# 4_cyber60-mx_periferals.net
KiCad netlist of a schematic drawn in Altium Designer
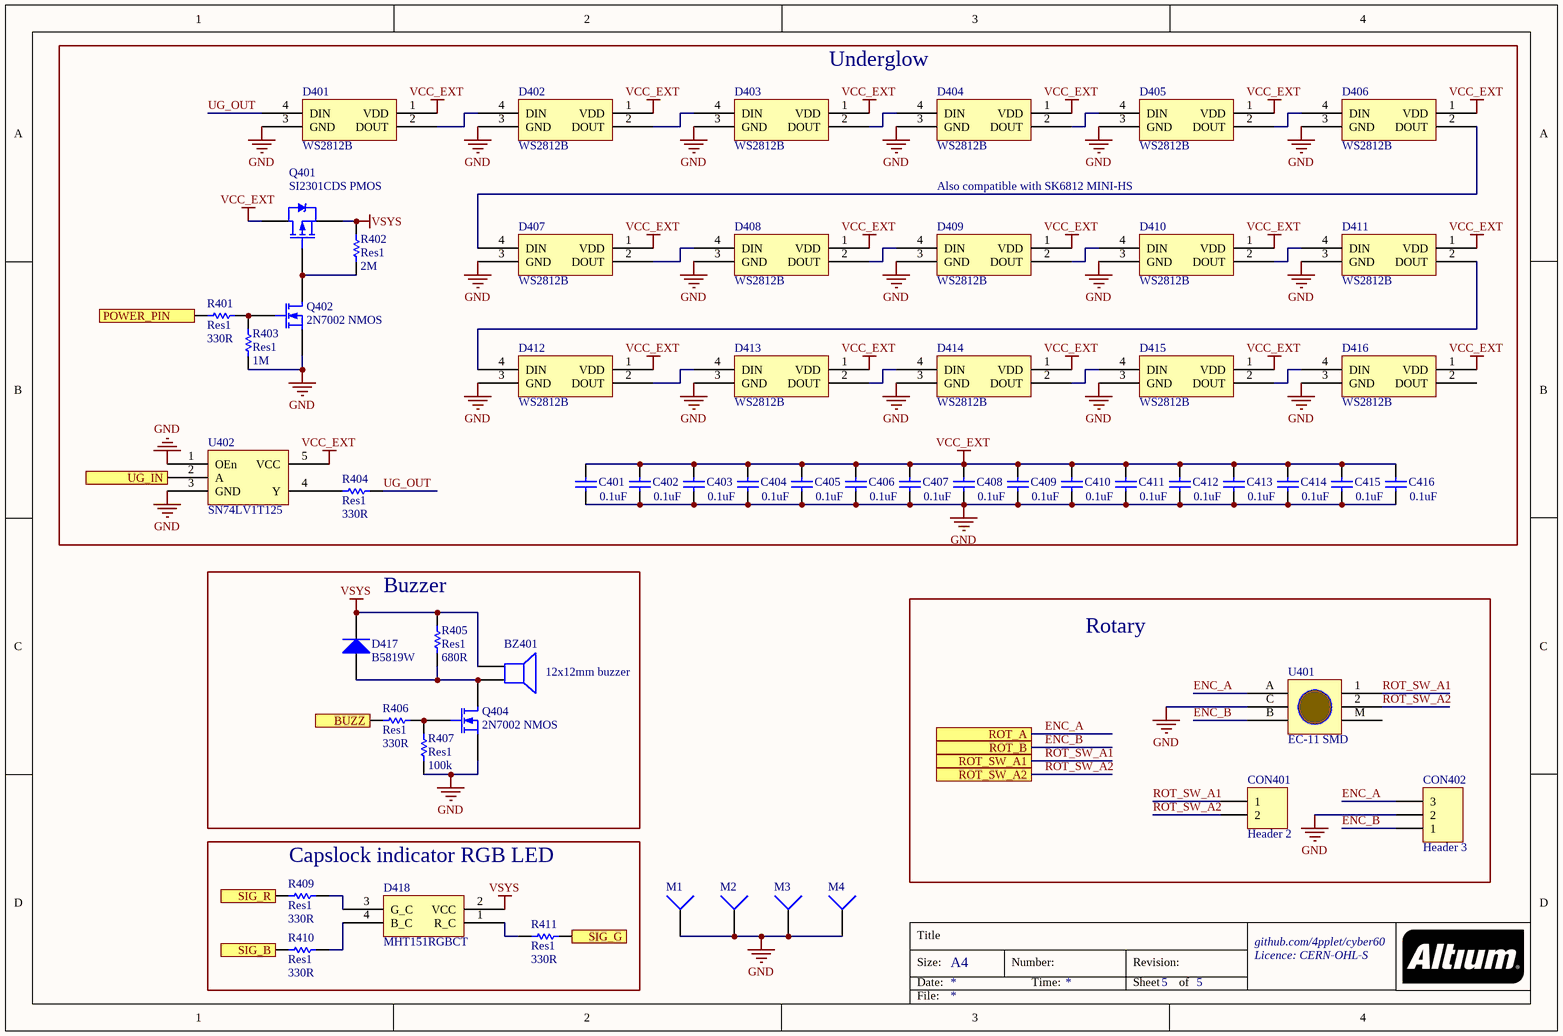
[diagram p0: 4_cyber60-mx_periferals.SchDoc]

(export (version "E")
  (design (tool "Eeschema 10.0.6"))
  (components
    (comp (ref "BZ401")
      (value "12x12mm buzzer")
      (footprint "buzzer 12x12")
      (description "Loudspeaker")
      (fields (field (name "LCSC PART #") "C409829") (field (name "MRF.PART") "YS-SBZ1230"))
      (libsource (lib "Miscellaneous Devices") (part "Speaker"))
    )
    (comp (ref "C401")
      (value "0.1uF")
      (footprint "C0603[1608]")
      (description "Capacitor")
      (fields (field (name "MFG") "KEMET") (field (name "LCSC PART #") "C14663"))
      (libsource (lib "Miscellaneous Devices") (part "Cap"))
    )
    (comp (ref "C402")
      (value "0.1uF")
      (footprint "C0603[1608]")
      (description "Capacitor")
      (fields (field (name "MFG") "KEMET") (field (name "LCSC PART #") "C14663"))
      (libsource (lib "Miscellaneous Devices") (part "Cap"))
    )
    (comp (ref "C403")
      (value "0.1uF")
      (footprint "C0603[1608]")
      (description "Capacitor")
      (fields (field (name "MFG") "KEMET") (field (name "LCSC PART #") "C14663"))
      (libsource (lib "Miscellaneous Devices") (part "Cap"))
    )
    (comp (ref "C404")
      (value "0.1uF")
      (footprint "C0603[1608]")
      (description "Capacitor")
      (fields (field (name "MFG") "KEMET") (field (name "LCSC PART #") "C14663"))
      (libsource (lib "Miscellaneous Devices") (part "Cap"))
    )
    (comp (ref "C405")
      (value "0.1uF")
      (footprint "C0603[1608]")
      (description "Capacitor")
      (fields (field (name "MFG") "KEMET") (field (name "LCSC PART #") "C14663"))
      (libsource (lib "Miscellaneous Devices") (part "Cap"))
    )
    (comp (ref "C406")
      (value "0.1uF")
      (footprint "C0603[1608]")
      (description "Capacitor")
      (fields (field (name "MFG") "KEMET") (field (name "LCSC PART #") "C14663"))
      (libsource (lib "Miscellaneous Devices") (part "Cap"))
    )
    (comp (ref "C407")
      (value "0.1uF")
      (footprint "C0603[1608]")
      (description "Capacitor")
      (fields (field (name "MFG") "KEMET") (field (name "LCSC PART #") "C14663"))
      (libsource (lib "Miscellaneous Devices") (part "Cap"))
    )
    (comp (ref "C408")
      (value "0.1uF")
      (footprint "C0603[1608]")
      (description "Capacitor")
      (fields (field (name "MFG") "KEMET") (field (name "LCSC PART #") "C14663"))
      (libsource (lib "Miscellaneous Devices") (part "Cap"))
    )
    (comp (ref "C409")
      (value "0.1uF")
      (footprint "C0603[1608]")
      (description "Capacitor")
      (fields (field (name "MFG") "KEMET") (field (name "LCSC PART #") "C14663"))
      (libsource (lib "Miscellaneous Devices") (part "Cap"))
    )
    (comp (ref "C410")
      (value "0.1uF")
      (footprint "C0603[1608]")
      (description "Capacitor")
      (fields (field (name "MFG") "KEMET") (field (name "LCSC PART #") "C14663"))
      (libsource (lib "Miscellaneous Devices") (part "Cap"))
    )
    (comp (ref "C411")
      (value "0.1uF")
      (footprint "C0603[1608]")
      (description "Capacitor")
      (fields (field (name "MFG") "KEMET") (field (name "LCSC PART #") "C14663"))
      (libsource (lib "Miscellaneous Devices") (part "Cap"))
    )
    (comp (ref "C412")
      (value "0.1uF")
      (footprint "C0603[1608]")
      (description "Capacitor")
      (fields (field (name "MFG") "KEMET") (field (name "LCSC PART #") "C14663"))
      (libsource (lib "Miscellaneous Devices") (part "Cap"))
    )
    (comp (ref "C413")
      (value "0.1uF")
      (footprint "C0603[1608]")
      (description "Capacitor")
      (fields (field (name "MFG") "KEMET") (field (name "LCSC PART #") "C14663"))
      (libsource (lib "Miscellaneous Devices") (part "Cap"))
    )
    (comp (ref "C414")
      (value "0.1uF")
      (footprint "C0603[1608]")
      (description "Capacitor")
      (fields (field (name "MFG") "KEMET") (field (name "LCSC PART #") "C14663"))
      (libsource (lib "Miscellaneous Devices") (part "Cap"))
    )
    (comp (ref "C415")
      (value "0.1uF")
      (footprint "C0603[1608]")
      (description "Capacitor")
      (fields (field (name "MFG") "KEMET") (field (name "LCSC PART #") "C14663"))
      (libsource (lib "Miscellaneous Devices") (part "Cap"))
    )
    (comp (ref "C416")
      (value "0.1uF")
      (footprint "C0603[1608]")
      (description "Capacitor")
      (fields (field (name "MFG") "KEMET") (field (name "LCSC PART #") "C14663"))
      (libsource (lib "Miscellaneous Devices") (part "Cap"))
    )
    (comp (ref "CON401")
      (value "Header 2")
      (footprint "HDR1X2")
      (description "Header, 2-Pin")
      (libsource (lib "Miscellaneous Connectors") (part "Header 2"))
    )
    (comp (ref "CON402")
      (value "Header 3")
      (footprint "HDR1X3")
      (description "Header, 3-Pin")
      (libsource (lib "Miscellaneous Connectors") (part "Header 3"))
    )
    (comp (ref "D401")
      (value "WS2812B")
      (footprint "WS2812B - 2020")
      (fields (field (name "LCSC PART #") "C965556") (field (name "MRF.PART") "WS2812C-2020"))
      (libsource (lib "Keebs") (part "WS2812B"))
    )
    (comp (ref "D402")
      (value "WS2812B")
      (footprint "WS2812B - 2020")
      (fields (field (name "LCSC PART #") "C965556") (field (name "MRF.PART") "WS2812C-2020"))
      (libsource (lib "Keebs") (part "WS2812B"))
    )
    (comp (ref "D403")
      (value "WS2812B")
      (footprint "WS2812B - 2020")
      (fields (field (name "LCSC PART #") "C965556") (field (name "MRF.PART") "WS2812C-2020"))
      (libsource (lib "Keebs") (part "WS2812B"))
    )
    (comp (ref "D404")
      (value "WS2812B")
      (footprint "WS2812B - 2020")
      (fields (field (name "LCSC PART #") "C965556") (field (name "MRF.PART") "WS2812C-2020"))
      (libsource (lib "Keebs") (part "WS2812B"))
    )
    (comp (ref "D405")
      (value "WS2812B")
      (footprint "WS2812B - 2020")
      (fields (field (name "LCSC PART #") "C965556") (field (name "MRF.PART") "WS2812C-2020"))
      (libsource (lib "Keebs") (part "WS2812B"))
    )
    (comp (ref "D406")
      (value "WS2812B")
      (footprint "WS2812B - 2020")
      (fields (field (name "LCSC PART #") "C965556") (field (name "MRF.PART") "WS2812C-2020"))
      (libsource (lib "Keebs") (part "WS2812B"))
    )
    (comp (ref "D407")
      (value "WS2812B")
      (footprint "WS2812B - 2020")
      (fields (field (name "LCSC PART #") "C965556") (field (name "MRF.PART") "WS2812C-2020"))
      (libsource (lib "Keebs") (part "WS2812B"))
    )
    (comp (ref "D408")
      (value "WS2812B")
      (footprint "WS2812B - 2020")
      (fields (field (name "LCSC PART #") "C965556") (field (name "MRF.PART") "WS2812C-2020"))
      (libsource (lib "Keebs") (part "WS2812B"))
    )
    (comp (ref "D409")
      (value "WS2812B")
      (footprint "WS2812B - 2020")
      (fields (field (name "LCSC PART #") "C965556") (field (name "MRF.PART") "WS2812C-2020"))
      (libsource (lib "Keebs") (part "WS2812B"))
    )
    (comp (ref "D410")
      (value "WS2812B")
      (footprint "WS2812B - 2020")
      (fields (field (name "LCSC PART #") "C965556") (field (name "MRF.PART") "WS2812C-2020"))
      (libsource (lib "Keebs") (part "WS2812B"))
    )
    (comp (ref "D411")
      (value "WS2812B")
      (footprint "WS2812B - 2020")
      (fields (field (name "LCSC PART #") "C965556") (field (name "MRF.PART") "WS2812C-2020"))
      (libsource (lib "Keebs") (part "WS2812B"))
    )
    (comp (ref "D412")
      (value "WS2812B")
      (footprint "WS2812B - 2020")
      (fields (field (name "LCSC PART #") "C965556") (field (name "MRF.PART") "WS2812C-2020"))
      (libsource (lib "Keebs") (part "WS2812B"))
    )
    (comp (ref "D413")
      (value "WS2812B")
      (footprint "WS2812B - 2020")
      (fields (field (name "LCSC PART #") "C965556") (field (name "MRF.PART") "WS2812C-2020"))
      (libsource (lib "Keebs") (part "WS2812B"))
    )
    (comp (ref "D414")
      (value "WS2812B")
      (footprint "WS2812B - 2020")
      (fields (field (name "LCSC PART #") "C965556") (field (name "MRF.PART") "WS2812C-2020"))
      (libsource (lib "Keebs") (part "WS2812B"))
    )
    (comp (ref "D415")
      (value "WS2812B")
      (footprint "WS2812B - 2020")
      (fields (field (name "LCSC PART #") "C965556") (field (name "MRF.PART") "WS2812C-2020"))
      (libsource (lib "Keebs") (part "WS2812B"))
    )
    (comp (ref "D416")
      (value "WS2812B")
      (footprint "WS2812B - 2020")
      (fields (field (name "LCSC PART #") "C965556") (field (name "MRF.PART") "WS2812C-2020"))
      (libsource (lib "Keebs") (part "WS2812B"))
    )
    (comp (ref "D417")
      (value "B5819W")
      (footprint "SOD-123")
      (description "Default Diode")
      (fields (field (name "LCSC PART #") "C8598"))
      (libsource (lib "Miscellaneous Devices") (part "Diode"))
    )
    (comp (ref "D418")
      (value "MHT151RGBCT")
      (footprint "MHT151RGBCT")
      (fields (field (name "LCSC PART #") "C2802677") (field (name "MRF.PART") "E6CC1205RGBC3UDA"))
      (libsource (lib "Keebs") (part "MHT151RGBCT"))
    )
    (comp (ref "M1")
      (value "Socket")
      (footprint "mounting_hole")
      (fields (field (name "PUBLISHER") "Altium Limited"))
      (libsource (lib "Miscellaneous Connectors") (part "Socket"))
    )
    (comp (ref "M2")
      (value "Socket")
      (footprint "mounting_hole")
      (fields (field (name "PUBLISHER") "Altium Limited"))
      (libsource (lib "Miscellaneous Connectors") (part "Socket"))
    )
    (comp (ref "M3")
      (value "Socket")
      (footprint "mounting_hole")
      (fields (field (name "PUBLISHER") "Altium Limited"))
      (libsource (lib "Miscellaneous Connectors") (part "Socket"))
    )
    (comp (ref "M4")
      (value "Socket")
      (footprint "mounting_hole")
      (fields (field (name "PUBLISHER") "Altium Limited"))
      (libsource (lib "Miscellaneous Connectors") (part "Socket"))
    )
    (comp (ref "Q401")
      (value "SI2301CDS PMOS")
      (footprint "SOT-23-3")
      (description "P-Channel Power MOSFET")
      (fields (field (name "MRF.PART") "SI2301CDS-T1-GE3") (field (name "LCSC PART #") "C10487"))
      (libsource (lib "Miscellaneous Devices") (part "PMOS-2"))
    )
    (comp (ref "Q402")
      (value "2N7002 NMOS")
      (footprint "SOT-23-3")
      (description "N-Channel MOSFET")
      (fields (field (name "LCSC PART #") "C8545") (field (name "MRF.PART") "2N7002"))
      (libsource (lib "Miscellaneous Devices") (part "MOSFET-N"))
    )
    (comp (ref "Q404")
      (value "2N7002 NMOS")
      (footprint "SOT-23-3")
      (description "N-Channel MOSFET")
      (fields (field (name "LCSC PART #") "C8545") (field (name "MRF.PART") "2N7002"))
      (libsource (lib "Miscellaneous Devices") (part "MOSFET-N"))
    )
    (comp (ref "R401")
      (value "Res1")
      (footprint "R0603[1608]")
      (description "Resistor")
      (fields
        (field (name "ALTIUM_VALUE") "330R")
        (field (name "LCSC PART #") "C23138")
        (field (name "MRF.PART") "0603WAF3300T5E")
      )
      (libsource (lib "Miscellaneous Devices") (part "Res1"))
    )
    (comp (ref "R402")
      (value "Res1")
      (footprint "R0603[1608]")
      (description "Resistor")
      (fields
        (field (name "ALTIUM_VALUE") "2M")
        (field (name "MRF.PART") "0603WAF2004T5E")
        (field (name "LCSC PART #") "C22976")
      )
      (libsource (lib "Miscellaneous Devices") (part "Res1"))
    )
    (comp (ref "R403")
      (value "Res1")
      (footprint "R0603[1608]")
      (description "Resistor")
      (fields
        (field (name "ALTIUM_VALUE") "1M")
        (field (name "MRF.PART") "0603WAF1004T5E")
        (field (name "LCSC PART #") "C22935")
      )
      (libsource (lib "Miscellaneous Devices") (part "Res1"))
    )
    (comp (ref "R404")
      (value "Res1")
      (footprint "R0603[1608]")
      (description "Resistor")
      (fields
        (field (name "ALTIUM_VALUE") "330R")
        (field (name "LCSC PART #") "C23138")
        (field (name "MRF.PART") "0603WAF3300T5E")
      )
      (libsource (lib "Miscellaneous Devices") (part "Res1"))
    )
    (comp (ref "R405")
      (value "Res1")
      (footprint "R0603[1608]")
      (description "Resistor")
      (fields
        (field (name "ALTIUM_VALUE") "680R")
        (field (name "MRF.PART") "0603WAF6800T5E")
        (field (name "LCSC PART #") "C23228")
      )
      (libsource (lib "Miscellaneous Devices") (part "Res1"))
    )
    (comp (ref "R406")
      (value "Res1")
      (footprint "R0603[1608]")
      (description "Resistor")
      (fields
        (field (name "ALTIUM_VALUE") "330R")
        (field (name "LCSC PART #") "C23138")
        (field (name "MRF.PART") "0603WAF3300T5E")
      )
      (libsource (lib "Miscellaneous Devices") (part "Res1"))
    )
    (comp (ref "R407")
      (value "Res1")
      (footprint "R0603[1608]")
      (description "Resistor")
      (fields
        (field (name "ALTIUM_VALUE") "100k")
        (field (name "MRF.PART") "0603WAF1003T5E")
        (field (name "LCSC PART #") "C25803")
      )
      (libsource (lib "Miscellaneous Devices") (part "Res1"))
    )
    (comp (ref "R409")
      (value "Res1")
      (footprint "R0603[1608]")
      (description "Resistor")
      (fields
        (field (name "ALTIUM_VALUE") "330R")
        (field (name "LCSC PART #") "C23138")
        (field (name "MRF.PART") "0603WAF3300T5E")
      )
      (libsource (lib "Miscellaneous Devices") (part "Res1"))
    )
    (comp (ref "R410")
      (value "Res1")
      (footprint "R0603[1608]")
      (description "Resistor")
      (fields
        (field (name "ALTIUM_VALUE") "330R")
        (field (name "LCSC PART #") "C23138")
        (field (name "MRF.PART") "0603WAF3300T5E")
      )
      (libsource (lib "Miscellaneous Devices") (part "Res1"))
    )
    (comp (ref "R411")
      (value "Res1")
      (footprint "R0603[1608]")
      (description "Resistor")
      (fields
        (field (name "ALTIUM_VALUE") "330R")
        (field (name "LCSC PART #") "C23138")
        (field (name "MRF.PART") "0603WAF3300T5E")
      )
      (libsource (lib "Miscellaneous Devices") (part "Res1"))
    )
    (comp (ref "U401") (value "EC-11 SMD") (footprint "EC11-SMD") (libsource (lib "Keebs") (part "EC-11")))
    (comp (ref "U402")
      (value "SN74LV1T125")
      (footprint "SOT-23-5")
      (description "SN74LV1T125 or SN74LV1T34. Connect OE to GND")
      (fields (field (name "LCSC PART #") "C473338") (field (name "MRF.PART") "SN74LV1T125DBVR"))
      (libsource (lib "Keebs") (part "SN74LV1T125"))
    )
  )
  (nets
    (net (code "1") (name "/BUZZ") (class "Default")
      (node (ref "R406") (pin "2") (pinfunction "2_2") (pintype "passive"))
    )
    (net (code "2") (name "/ENC_A") (class "Default")
      (node (ref "CON402") (pin "3") (pinfunction "3_3") (pintype "passive"))
      (node (ref "U401") (pin "A") (pinfunction "B_A") (pintype "passive"))
    )
    (net (code "3") (name "/ENC_B") (class "Default")
      (node (ref "CON402") (pin "1") (pinfunction "1_1") (pintype "passive"))
      (node (ref "U401") (pin "B") (pinfunction "B_B") (pintype "passive"))
    )
    (net (code "4") (name "/POWER_PIN") (class "Default")
      (node (ref "R401") (pin "1") (pinfunction "1_1") (pintype "passive"))
    )
    (net (code "5") (name "/ROT_SW_A1") (class "Default")
      (node (ref "CON401") (pin "1") (pinfunction "1_1") (pintype "passive"))
      (node (ref "U401") (pin "1") (pinfunction "1_1") (pintype "passive"))
    )
    (net (code "6") (name "/ROT_SW_A2") (class "Default")
      (node (ref "CON401") (pin "2") (pinfunction "2_2") (pintype "passive"))
      (node (ref "U401") (pin "2") (pinfunction "2_2") (pintype "passive"))
    )
    (net (code "7") (name "/SIG_B") (class "Default")
      (node (ref "R410") (pin "2") (pinfunction "2_2") (pintype "passive"))
    )
    (net (code "8") (name "/SIG_G") (class "Default")
      (node (ref "R411") (pin "1") (pinfunction "1_1") (pintype "passive"))
    )
    (net (code "9") (name "/SIG_R") (class "Default")
      (node (ref "R409") (pin "2") (pinfunction "2_2") (pintype "passive"))
    )
    (net (code "10") (name "/UG_IN") (class "Default")
      (node (ref "U402") (pin "2") (pinfunction "A_2") (pintype "passive"))
    )
    (net (code "11") (name "/UG_OUT") (class "Default")
      (node (ref "D401") (pin "4") (pinfunction "DIN_4") (pintype "passive"))
      (node (ref "R404") (pin "1") (pinfunction "1_1") (pintype "passive"))
    )
    (net (code "12") (name "GND") (class "Default")
      (node (ref "C401") (pin "1") (pinfunction "1_1") (pintype "passive"))
      (node (ref "C402") (pin "1") (pinfunction "1_1") (pintype "passive"))
      (node (ref "C403") (pin "1") (pinfunction "1_1") (pintype "passive"))
      (node (ref "C404") (pin "1") (pinfunction "1_1") (pintype "passive"))
      (node (ref "C405") (pin "1") (pinfunction "1_1") (pintype "passive"))
      (node (ref "C406") (pin "1") (pinfunction "1_1") (pintype "passive"))
      (node (ref "C407") (pin "1") (pinfunction "1_1") (pintype "passive"))
      (node (ref "C408") (pin "1") (pinfunction "1_1") (pintype "passive"))
      (node (ref "C409") (pin "1") (pinfunction "1_1") (pintype "passive"))
      (node (ref "C410") (pin "1") (pinfunction "1_1") (pintype "passive"))
      (node (ref "C411") (pin "1") (pinfunction "1_1") (pintype "passive"))
      (node (ref "C412") (pin "1") (pinfunction "1_1") (pintype "passive"))
      (node (ref "C413") (pin "1") (pinfunction "1_1") (pintype "passive"))
      (node (ref "C414") (pin "1") (pinfunction "1_1") (pintype "passive"))
      (node (ref "C415") (pin "1") (pinfunction "1_1") (pintype "passive"))
      (node (ref "C416") (pin "1") (pinfunction "1_1") (pintype "passive"))
      (node (ref "CON402") (pin "2") (pinfunction "2_2") (pintype "passive"))
      (node (ref "D401") (pin "3") (pinfunction "GND_3") (pintype "passive"))
      (node (ref "D402") (pin "3") (pinfunction "GND_3") (pintype "passive"))
      (node (ref "D403") (pin "3") (pinfunction "GND_3") (pintype "passive"))
      (node (ref "D404") (pin "3") (pinfunction "GND_3") (pintype "passive"))
      (node (ref "D405") (pin "3") (pinfunction "GND_3") (pintype "passive"))
      (node (ref "D406") (pin "3") (pinfunction "GND_3") (pintype "passive"))
      (node (ref "D407") (pin "3") (pinfunction "GND_3") (pintype "passive"))
      (node (ref "D408") (pin "3") (pinfunction "GND_3") (pintype "passive"))
      (node (ref "D409") (pin "3") (pinfunction "GND_3") (pintype "passive"))
      (node (ref "D410") (pin "3") (pinfunction "GND_3") (pintype "passive"))
      (node (ref "D411") (pin "3") (pinfunction "GND_3") (pintype "passive"))
      (node (ref "D412") (pin "3") (pinfunction "GND_3") (pintype "passive"))
      (node (ref "D413") (pin "3") (pinfunction "GND_3") (pintype "passive"))
      (node (ref "D414") (pin "3") (pinfunction "GND_3") (pintype "passive"))
      (node (ref "D415") (pin "3") (pinfunction "GND_3") (pintype "passive"))
      (node (ref "D416") (pin "3") (pinfunction "GND_3") (pintype "passive"))
      (node (ref "M1") (pin "1") (pinfunction "1_1") (pintype "passive"))
      (node (ref "M2") (pin "1") (pinfunction "1_1") (pintype "passive"))
      (node (ref "M3") (pin "1") (pinfunction "1_1") (pintype "passive"))
      (node (ref "M4") (pin "1") (pinfunction "1_1") (pintype "passive"))
      (node (ref "Q402") (pin "2") (pinfunction "S_2") (pintype "passive"))
      (node (ref "Q404") (pin "2") (pinfunction "S_2") (pintype "passive"))
      (node (ref "R403") (pin "2") (pinfunction "2_2") (pintype "passive"))
      (node (ref "R407") (pin "2") (pinfunction "2_2") (pintype "passive"))
      (node (ref "U401") (pin "C") (pinfunction "C_C") (pintype "passive"))
      (node (ref "U402") (pin "1") (pinfunction "OEn_1") (pintype "passive"))
      (node (ref "U402") (pin "3") (pinfunction "GND_3") (pintype "passive"))
    )
    (net (code "13") (name "Net-(D401-DOUT)") (class "Default")
      (node (ref "D401") (pin "2") (pinfunction "DOUT_2") (pintype "passive"))
      (node (ref "D402") (pin "4") (pinfunction "DIN_4") (pintype "passive"))
    )
    (net (code "14") (name "Net-(D402-DOUT)") (class "Default")
      (node (ref "D402") (pin "2") (pinfunction "DOUT_2") (pintype "passive"))
      (node (ref "D403") (pin "4") (pinfunction "DIN_4") (pintype "passive"))
    )
    (net (code "15") (name "Net-(D403-DOUT)") (class "Default")
      (node (ref "D403") (pin "2") (pinfunction "DOUT_2") (pintype "passive"))
      (node (ref "D404") (pin "4") (pinfunction "DIN_4") (pintype "passive"))
    )
    (net (code "16") (name "Net-(D404-DOUT)") (class "Default")
      (node (ref "D404") (pin "2") (pinfunction "DOUT_2") (pintype "passive"))
      (node (ref "D405") (pin "4") (pinfunction "DIN_4") (pintype "passive"))
    )
    (net (code "17") (name "Net-(D405-DOUT)") (class "Default")
      (node (ref "D405") (pin "2") (pinfunction "DOUT_2") (pintype "passive"))
      (node (ref "D406") (pin "4") (pinfunction "DIN_4") (pintype "passive"))
    )
    (net (code "18") (name "Net-(D406-DOUT)") (class "Default")
      (node (ref "D406") (pin "2") (pinfunction "DOUT_2") (pintype "passive"))
      (node (ref "D407") (pin "4") (pinfunction "DIN_4") (pintype "passive"))
    )
    (net (code "19") (name "Net-(D407-DOUT)") (class "Default")
      (node (ref "D407") (pin "2") (pinfunction "DOUT_2") (pintype "passive"))
      (node (ref "D408") (pin "4") (pinfunction "DIN_4") (pintype "passive"))
    )
    (net (code "20") (name "Net-(D408-DOUT)") (class "Default")
      (node (ref "D408") (pin "2") (pinfunction "DOUT_2") (pintype "passive"))
      (node (ref "D409") (pin "4") (pinfunction "DIN_4") (pintype "passive"))
    )
    (net (code "21") (name "Net-(D409-DOUT)") (class "Default")
      (node (ref "D409") (pin "2") (pinfunction "DOUT_2") (pintype "passive"))
      (node (ref "D410") (pin "4") (pinfunction "DIN_4") (pintype "passive"))
    )
    (net (code "22") (name "Net-(D410-DOUT)") (class "Default")
      (node (ref "D410") (pin "2") (pinfunction "DOUT_2") (pintype "passive"))
      (node (ref "D411") (pin "4") (pinfunction "DIN_4") (pintype "passive"))
    )
    (net (code "23") (name "Net-(D411-DOUT)") (class "Default")
      (node (ref "D411") (pin "2") (pinfunction "DOUT_2") (pintype "passive"))
      (node (ref "D412") (pin "4") (pinfunction "DIN_4") (pintype "passive"))
    )
    (net (code "24") (name "Net-(D412-DOUT)") (class "Default")
      (node (ref "D412") (pin "2") (pinfunction "DOUT_2") (pintype "passive"))
      (node (ref "D413") (pin "4") (pinfunction "DIN_4") (pintype "passive"))
    )
    (net (code "25") (name "Net-(D413-DOUT)") (class "Default")
      (node (ref "D413") (pin "2") (pinfunction "DOUT_2") (pintype "passive"))
      (node (ref "D414") (pin "4") (pinfunction "DIN_4") (pintype "passive"))
    )
    (net (code "26") (name "Net-(D414-DOUT)") (class "Default")
      (node (ref "D414") (pin "2") (pinfunction "DOUT_2") (pintype "passive"))
      (node (ref "D415") (pin "4") (pinfunction "DIN_4") (pintype "passive"))
    )
    (net (code "27") (name "Net-(D415-DOUT)") (class "Default")
      (node (ref "D415") (pin "2") (pinfunction "DOUT_2") (pintype "passive"))
      (node (ref "D416") (pin "4") (pinfunction "DIN_4") (pintype "passive"))
    )
    (net (code "28") (name "Net-(D417-A)") (class "Default")
      (node (ref "BZ401") (pin "2") (pinfunction "2_2") (pintype "passive"))
      (node (ref "D417") (pin "1") (pinfunction "A_1") (pintype "passive"))
      (node (ref "Q404") (pin "3") (pinfunction "D_3") (pintype "passive"))
      (node (ref "R405") (pin "2") (pinfunction "2_2") (pintype "passive"))
    )
    (net (code "29") (name "Net-(D418-B_C)") (class "Default")
      (node (ref "D418") (pin "4") (pinfunction "B_C_4") (pintype "passive"))
      (node (ref "R410") (pin "1") (pinfunction "1_1") (pintype "passive"))
    )
    (net (code "30") (name "Net-(D418-G_C)") (class "Default")
      (node (ref "D418") (pin "3") (pinfunction "G_C_3") (pintype "passive"))
      (node (ref "R409") (pin "1") (pinfunction "1_1") (pintype "passive"))
    )
    (net (code "31") (name "Net-(D418-R_C)") (class "Default")
      (node (ref "D418") (pin "1") (pinfunction "R_C_1") (pintype "passive"))
      (node (ref "R411") (pin "2") (pinfunction "2_2") (pintype "passive"))
    )
    (net (code "32") (name "Net-(Q401-G)") (class "Default")
      (node (ref "Q401") (pin "1") (pinfunction "G_1") (pintype "passive"))
      (node (ref "Q402") (pin "3") (pinfunction "D_3") (pintype "passive"))
      (node (ref "R402") (pin "1") (pinfunction "1_1") (pintype "passive"))
    )
    (net (code "33") (name "Net-(Q402-G)") (class "Default")
      (node (ref "Q402") (pin "1") (pinfunction "G_1") (pintype "passive"))
      (node (ref "R401") (pin "2") (pinfunction "2_2") (pintype "passive"))
      (node (ref "R403") (pin "1") (pinfunction "1_1") (pintype "passive"))
    )
    (net (code "34") (name "Net-(Q404-G)") (class "Default")
      (node (ref "Q404") (pin "1") (pinfunction "G_1") (pintype "passive"))
      (node (ref "R406") (pin "1") (pinfunction "1_1") (pintype "passive"))
      (node (ref "R407") (pin "1") (pinfunction "1_1") (pintype "passive"))
    )
    (net (code "35") (name "Net-(U402-Y)") (class "Default")
      (node (ref "R404") (pin "2") (pinfunction "2_2") (pintype "passive"))
      (node (ref "U402") (pin "4") (pinfunction "Y_4") (pintype "passive"))
    )
    (net (code "36") (name "VCC_EXT") (class "Default")
      (node (ref "C401") (pin "2") (pinfunction "2_2") (pintype "passive"))
      (node (ref "C402") (pin "2") (pinfunction "2_2") (pintype "passive"))
      (node (ref "C403") (pin "2") (pinfunction "2_2") (pintype "passive"))
      (node (ref "C404") (pin "2") (pinfunction "2_2") (pintype "passive"))
      (node (ref "C405") (pin "2") (pinfunction "2_2") (pintype "passive"))
      (node (ref "C406") (pin "2") (pinfunction "2_2") (pintype "passive"))
      (node (ref "C407") (pin "2") (pinfunction "2_2") (pintype "passive"))
      (node (ref "C408") (pin "2") (pinfunction "2_2") (pintype "passive"))
      (node (ref "C409") (pin "2") (pinfunction "2_2") (pintype "passive"))
      (node (ref "C410") (pin "2") (pinfunction "2_2") (pintype "passive"))
      (node (ref "C411") (pin "2") (pinfunction "2_2") (pintype "passive"))
      (node (ref "C412") (pin "2") (pinfunction "2_2") (pintype "passive"))
      (node (ref "C413") (pin "2") (pinfunction "2_2") (pintype "passive"))
      (node (ref "C414") (pin "2") (pinfunction "2_2") (pintype "passive"))
      (node (ref "C415") (pin "2") (pinfunction "2_2") (pintype "passive"))
      (node (ref "C416") (pin "2") (pinfunction "2_2") (pintype "passive"))
      (node (ref "D401") (pin "1") (pinfunction "VDD_1") (pintype "passive"))
      (node (ref "D402") (pin "1") (pinfunction "VDD_1") (pintype "passive"))
      (node (ref "D403") (pin "1") (pinfunction "VDD_1") (pintype "passive"))
      (node (ref "D404") (pin "1") (pinfunction "VDD_1") (pintype "passive"))
      (node (ref "D405") (pin "1") (pinfunction "VDD_1") (pintype "passive"))
      (node (ref "D406") (pin "1") (pinfunction "VDD_1") (pintype "passive"))
      (node (ref "D407") (pin "1") (pinfunction "VDD_1") (pintype "passive"))
      (node (ref "D408") (pin "1") (pinfunction "VDD_1") (pintype "passive"))
      (node (ref "D409") (pin "1") (pinfunction "VDD_1") (pintype "passive"))
      (node (ref "D410") (pin "1") (pinfunction "VDD_1") (pintype "passive"))
      (node (ref "D411") (pin "1") (pinfunction "VDD_1") (pintype "passive"))
      (node (ref "D412") (pin "1") (pinfunction "VDD_1") (pintype "passive"))
      (node (ref "D413") (pin "1") (pinfunction "VDD_1") (pintype "passive"))
      (node (ref "D414") (pin "1") (pinfunction "VDD_1") (pintype "passive"))
      (node (ref "D415") (pin "1") (pinfunction "VDD_1") (pintype "passive"))
      (node (ref "D416") (pin "1") (pinfunction "VDD_1") (pintype "passive"))
      (node (ref "Q401") (pin "3") (pinfunction "D_3") (pintype "passive"))
      (node (ref "U402") (pin "5") (pinfunction "VCC_5") (pintype "passive"))
    )
    (net (code "37") (name "VSYS") (class "Default")
      (node (ref "BZ401") (pin "1") (pinfunction "1_1") (pintype "passive"))
      (node (ref "D417") (pin "2") (pinfunction "K_2") (pintype "passive"))
      (node (ref "D418") (pin "2") (pinfunction "VCC_2") (pintype "passive"))
      (node (ref "Q401") (pin "2") (pinfunction "S_2") (pintype "passive"))
      (node (ref "R402") (pin "2") (pinfunction "2_2") (pintype "passive"))
      (node (ref "R405") (pin "1") (pinfunction "1_1") (pintype "passive"))
    )
    (net (code "38") (name "unconnected-(D416-DOUT-Pad2)") (class "Default")
      (node (ref "D416") (pin "2") (pinfunction "DOUT_2") (pintype "passive"))
    )
    (net (code "39") (name "unconnected-(U401-PadM)") (class "Default")
      (node (ref "U401") (pin "M") (pinfunction "M_M") (pintype "passive"))
    )
  )
)
